# EthCtrlMeter.net
KiCad netlist of a schematic drawn in EAGLE
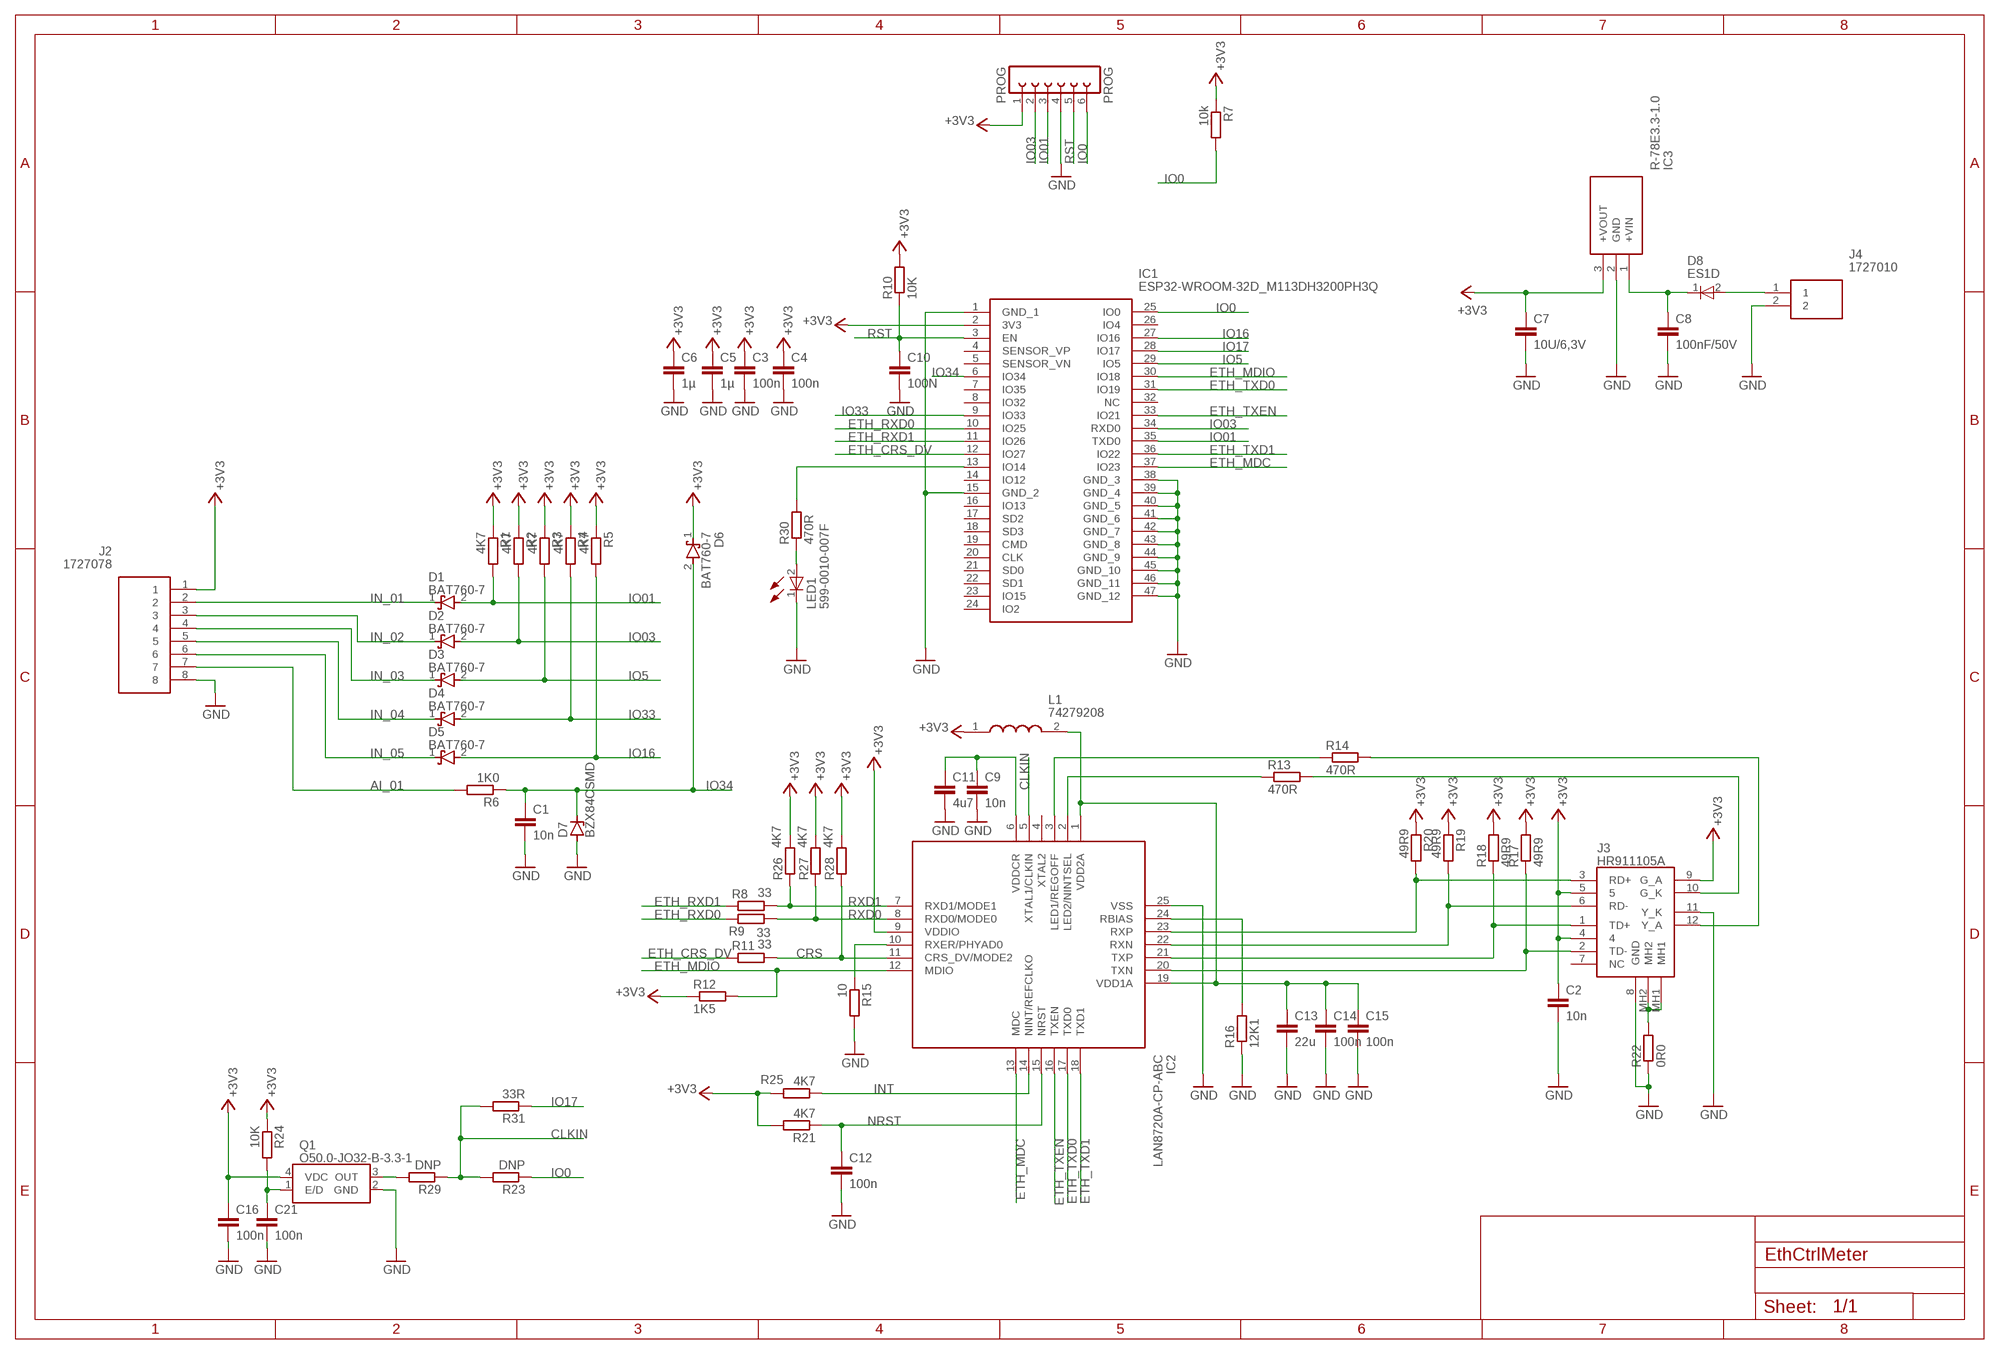
[diagram p0: schematic, sheet 1]

(export (version "E")
  (design (tool "Eeschema 10.0.6"))
  (components
    (comp (ref "C1")
      (value "10n")
      (footprint "eagle-import:C0603")
      (libsource (lib "eagle-import") (part "C-EUC0603"))
    )
    (comp (ref "C2")
      (value "10n")
      (footprint "eagle-import:C0603")
      (libsource (lib "eagle-import") (part "C-EUC0603"))
    )
    (comp (ref "C3")
      (value "100n")
      (footprint "eagle-import:C0603")
      (libsource (lib "eagle-import") (part "C-EUC0603"))
    )
    (comp (ref "C4")
      (value "100n")
      (footprint "eagle-import:C0603")
      (libsource (lib "eagle-import") (part "C-EUC0603"))
    )
    (comp (ref "C5")
      (value "1µ")
      (footprint "eagle-import:C0603")
      (libsource (lib "eagle-import") (part "C-EUC0603"))
    )
    (comp (ref "C6")
      (value "1µ")
      (footprint "eagle-import:C0603")
      (libsource (lib "eagle-import") (part "C-EUC0603"))
    )
    (comp (ref "C7")
      (value "10U/6,3V")
      (footprint "eagle-import:C0603")
      (libsource (lib "eagle-import") (part "C-EUC0603"))
    )
    (comp (ref "C8")
      (value "100nF/50V")
      (footprint "eagle-import:C0603")
      (libsource (lib "eagle-import") (part "C-EUC0603"))
    )
    (comp (ref "C9")
      (value "10n")
      (footprint "eagle-import:C0603")
      (libsource (lib "eagle-import") (part "C-EUC0603"))
    )
    (comp (ref "C10")
      (value "100N")
      (footprint "eagle-import:C0603")
      (libsource (lib "eagle-import") (part "C-EUC0603"))
    )
    (comp (ref "C11")
      (value "4u7")
      (footprint "eagle-import:C0603")
      (libsource (lib "eagle-import") (part "C-EUC0603"))
    )
    (comp (ref "C12")
      (value "100n")
      (footprint "eagle-import:C0603")
      (libsource (lib "eagle-import") (part "C-EUC0603"))
    )
    (comp (ref "C13")
      (value "22u")
      (footprint "eagle-import:C0603")
      (libsource (lib "eagle-import") (part "C-EUC0603"))
    )
    (comp (ref "C14")
      (value "100n")
      (footprint "eagle-import:C0603")
      (libsource (lib "eagle-import") (part "C-EUC0603"))
    )
    (comp (ref "C15")
      (value "100n")
      (footprint "eagle-import:C0603")
      (libsource (lib "eagle-import") (part "C-EUC0603"))
    )
    (comp (ref "C16")
      (value "100n")
      (footprint "eagle-import:C0603")
      (libsource (lib "eagle-import") (part "C-EUC0603"))
    )
    (comp (ref "C21")
      (value "100n")
      (footprint "eagle-import:C0603")
      (libsource (lib "eagle-import") (part "C-EUC0603"))
    )
    (comp (ref "D1")
      (value "BAT760-7")
      (footprint "eagle-import:SOD2513X120N")
      (fields (field (name "MOUSER_PART_NUMBER") "621-BAT760-7"))
      (libsource (lib "eagle-import") (part "BAT760-7"))
    )
    (comp (ref "D2")
      (value "BAT760-7")
      (footprint "eagle-import:SOD2513X120N")
      (fields (field (name "MOUSER_PART_NUMBER") "621-BAT760-7"))
      (libsource (lib "eagle-import") (part "BAT760-7"))
    )
    (comp (ref "D3")
      (value "BAT760-7")
      (footprint "eagle-import:SOD2513X120N")
      (fields (field (name "MOUSER_PART_NUMBER") "621-BAT760-7"))
      (libsource (lib "eagle-import") (part "BAT760-7"))
    )
    (comp (ref "D4")
      (value "BAT760-7")
      (footprint "eagle-import:SOD2513X120N")
      (fields (field (name "MOUSER_PART_NUMBER") "621-BAT760-7"))
      (libsource (lib "eagle-import") (part "BAT760-7"))
    )
    (comp (ref "D5")
      (value "BAT760-7")
      (footprint "eagle-import:SOD2513X120N")
      (fields (field (name "MOUSER_PART_NUMBER") "621-BAT760-7"))
      (libsource (lib "eagle-import") (part "BAT760-7"))
    )
    (comp (ref "D6")
      (value "BAT760-7")
      (footprint "eagle-import:SOD2513X120N")
      (fields (field (name "MOUSER_PART_NUMBER") "621-BAT760-7"))
      (libsource (lib "eagle-import") (part "BAT760-7"))
    )
    (comp (ref "D7")
      (value "BZX84CSMD")
      (footprint "eagle-import:TO236")
      (libsource (lib "eagle-import") (part "BZX84CSMD"))
    )
    (comp (ref "D8")
      (value "ES1D")
      (footprint "eagle-import:SODFL3618X143N")
      (fields
        (field (name "ARROW_PART_NUMBER") "ES1DL R3G")
        (field (name "MOUSER_PART_NUMBER") "821-ES1DLR3G")
      )
      (libsource (lib "eagle-import") (part "ES1DL_R3G"))
    )
    (comp (ref "IC1")
      (value "ESP32-WROOM-32D_M113DH3200PH3Q")
      (footprint "eagle-import:ESP32WROOM32DM113DH3200PH3Q0")
      (fields
        (field (name "MANUFACTURER_PART_NUMBER") "ESP32-WROOM-32D(M113DH3200PH3Q0)")
        (field (name "MOUSER_PART_NUMBER") "356-ESP32WROOM-32D")
      )
      (libsource (lib "eagle-import") (part "ESP32-WROOM-32D_M113DH3200PH3Q"))
    )
    (comp (ref "IC2")
      (value "LAN8720A-CP-ABC")
      (footprint "eagle-import:QFN50P400X400X100-25N")
      (fields (field (name "MOUSER_PART_NUMBER") "579-LAN8720ACPABC"))
      (libsource (lib "eagle-import") (part "LAN8720A-CP-ABC"))
    )
    (comp (ref "IC3")
      (value "R-78E3.3-1.0")
      (footprint "eagle-import:R78E3310")
      (fields (field (name "MOUSER_PART_NUMBER") "919-R-78E3.3-1.0"))
      (libsource (lib "eagle-import") (part "R-78E3.3-1.0"))
    )
    (comp (ref "J2")
      (value "1727078")
      (footprint "eagle-import:1727078")
      (fields (field (name "MOUSER_PART_NUMBER") "651-1727078"))
      (libsource (lib "eagle-import") (part "1727078"))
    )
    (comp (ref "J3")
      (value "HR911105A")
      (footprint "eagle-import:HR911105A")
      (libsource (lib "eagle-import") (part "HR911105A"))
    )
    (comp (ref "J4")
      (value "1727010")
      (footprint "eagle-import:1727010")
      (fields (field (name "MOUSER_PART_NUMBER") "651-1727010"))
      (libsource (lib "eagle-import") (part "1727010"))
    )
    (comp (ref "L1")
      (value "74279208")
      (footprint "eagle-import:CAPC2012X90N")
      (fields (field (name "MOUSER_PART_NUMBER") "710-74279208"))
      (libsource (lib "eagle-import") (part "74279208"))
    )
    (comp (ref "LED1")
      (value "599-0010-007F")
      (footprint "eagle-import:LEDM168X70N")
      (fields (field (name "MOUSER_PART_NUMBER") "645-599-0010-007F"))
      (libsource (lib "eagle-import") (part "599-0010-007F"))
    )
    (comp (ref "PROG")
      (value "PROG")
      (footprint "eagle-import:FE06")
      (libsource (lib "eagle-import") (part "FE06-1"))
    )
    (comp (ref "Q1")
      (value "O50.0-JO32-B-3.3-1")
      (footprint "eagle-import:O200JO32B1V31T1LF")
      (libsource (lib "eagle-import") (part "O50.0-JO32-B-3.3-1"))
    )
    (comp (ref "R1")
      (value "4K7")
      (footprint "eagle-import:R0603")
      (libsource (lib "eagle-import") (part "R-EU_R0603"))
    )
    (comp (ref "R2")
      (value "4K7")
      (footprint "eagle-import:R0603")
      (libsource (lib "eagle-import") (part "R-EU_R0603"))
    )
    (comp (ref "R3")
      (value "4K7")
      (footprint "eagle-import:R0603")
      (libsource (lib "eagle-import") (part "R-EU_R0603"))
    )
    (comp (ref "R4")
      (value "4K7")
      (footprint "eagle-import:R0603")
      (libsource (lib "eagle-import") (part "R-EU_R0603"))
    )
    (comp (ref "R5")
      (value "4K7")
      (footprint "eagle-import:R0603")
      (libsource (lib "eagle-import") (part "R-EU_R0603"))
    )
    (comp (ref "R6")
      (value "1K0")
      (footprint "eagle-import:R0603")
      (libsource (lib "eagle-import") (part "R-EU_R0603"))
    )
    (comp (ref "R7")
      (value "10k")
      (footprint "eagle-import:R0603")
      (libsource (lib "eagle-import") (part "R-EU_R0603"))
    )
    (comp (ref "R8")
      (value "33")
      (footprint "eagle-import:R0603")
      (libsource (lib "eagle-import") (part "R-EU_R0603"))
    )
    (comp (ref "R9")
      (value "33")
      (footprint "eagle-import:R0603")
      (libsource (lib "eagle-import") (part "R-EU_R0603"))
    )
    (comp (ref "R10")
      (value "10K")
      (footprint "eagle-import:R0603")
      (libsource (lib "eagle-import") (part "R-EU_R0603"))
    )
    (comp (ref "R11")
      (value "33")
      (footprint "eagle-import:R0603")
      (libsource (lib "eagle-import") (part "R-EU_R0603"))
    )
    (comp (ref "R12")
      (value "1K5")
      (footprint "eagle-import:R0603")
      (libsource (lib "eagle-import") (part "R-EU_R0603"))
    )
    (comp (ref "R13")
      (value "470R")
      (footprint "eagle-import:R0603")
      (libsource (lib "eagle-import") (part "R-EU_R0603"))
    )
    (comp (ref "R14")
      (value "470R")
      (footprint "eagle-import:R0603")
      (libsource (lib "eagle-import") (part "R-EU_R0603"))
    )
    (comp (ref "R15")
      (value "10")
      (footprint "eagle-import:R0603")
      (libsource (lib "eagle-import") (part "R-EU_R0603"))
    )
    (comp (ref "R16")
      (value "12K1")
      (footprint "eagle-import:R0603")
      (libsource (lib "eagle-import") (part "R-EU_R0603"))
    )
    (comp (ref "R17")
      (value "49R9")
      (footprint "eagle-import:R0603")
      (libsource (lib "eagle-import") (part "R-EU_R0603"))
    )
    (comp (ref "R18")
      (value "49R9")
      (footprint "eagle-import:R0603")
      (libsource (lib "eagle-import") (part "R-EU_R0603"))
    )
    (comp (ref "R19")
      (value "49R9")
      (footprint "eagle-import:R0603")
      (libsource (lib "eagle-import") (part "R-EU_R0603"))
    )
    (comp (ref "R20")
      (value "49R9")
      (footprint "eagle-import:R0603")
      (libsource (lib "eagle-import") (part "R-EU_R0603"))
    )
    (comp (ref "R21")
      (value "4K7")
      (footprint "eagle-import:R0603")
      (libsource (lib "eagle-import") (part "R-EU_R0603"))
    )
    (comp (ref "R22")
      (value "0R0")
      (footprint "eagle-import:R0603")
      (libsource (lib "eagle-import") (part "R-EU_R0603"))
    )
    (comp (ref "R23")
      (value "DNP")
      (footprint "eagle-import:R0603")
      (libsource (lib "eagle-import") (part "R-EU_R0603"))
    )
    (comp (ref "R24")
      (value "10K")
      (footprint "eagle-import:R0603")
      (libsource (lib "eagle-import") (part "R-EU_R0603"))
    )
    (comp (ref "R25")
      (value "4K7")
      (footprint "eagle-import:R0603")
      (libsource (lib "eagle-import") (part "R-EU_R0603"))
    )
    (comp (ref "R26")
      (value "4K7")
      (footprint "eagle-import:R0603")
      (libsource (lib "eagle-import") (part "R-EU_R0603"))
    )
    (comp (ref "R27")
      (value "4K7")
      (footprint "eagle-import:R0603")
      (libsource (lib "eagle-import") (part "R-EU_R0603"))
    )
    (comp (ref "R28")
      (value "4K7")
      (footprint "eagle-import:R0603")
      (libsource (lib "eagle-import") (part "R-EU_R0603"))
    )
    (comp (ref "R29")
      (value "DNP")
      (footprint "eagle-import:R0603")
      (libsource (lib "eagle-import") (part "R-EU_R0603"))
    )
    (comp (ref "R30")
      (value "470R")
      (footprint "eagle-import:R0603")
      (libsource (lib "eagle-import") (part "R-EU_R0603"))
    )
    (comp (ref "R31")
      (value "33R")
      (footprint "eagle-import:R0603")
      (libsource (lib "eagle-import") (part "R-EU_R0603"))
    )
  )
  (nets
    (net (code "1") (name "+3V3") (class "Default")
      (node (ref "C16") (pin "1") (pinfunction "1_1") (pintype "passive"))
      (node (ref "C2") (pin "1") (pinfunction "1_1") (pintype "passive"))
      (node (ref "C3") (pin "1") (pinfunction "1_1") (pintype "passive"))
      (node (ref "C4") (pin "1") (pinfunction "1_1") (pintype "passive"))
      (node (ref "C5") (pin "1") (pinfunction "1_1") (pintype "passive"))
      (node (ref "C6") (pin "1") (pinfunction "1_1") (pintype "passive"))
      (node (ref "C7") (pin "1") (pinfunction "1_1") (pintype "passive"))
      (node (ref "D6") (pin "1") (pinfunction "K_1") (pintype "passive"))
      (node (ref "IC1") (pin "2") (pinfunction "3V3_2") (pintype "bidirectional"))
      (node (ref "IC2") (pin "9") (pinfunction "VDDIO_9") (pintype "bidirectional"))
      (node (ref "IC3") (pin "3") (pinfunction "+VOUT_3") (pintype "bidirectional"))
      (node (ref "J2") (pin "1") (pinfunction "1_1") (pintype "bidirectional"))
      (node (ref "J3") (pin "4") (pinfunction "4_4") (pintype "bidirectional"))
      (node (ref "J3") (pin "5") (pinfunction "5_5") (pintype "bidirectional"))
      (node (ref "J3") (pin "9") (pinfunction "G_A_9") (pintype "bidirectional"))
      (node (ref "L1") (pin "1") (pinfunction "1_1") (pintype "bidirectional"))
      (node (ref "PROG") (pin "1") (pinfunction "1_1") (pintype "passive"))
      (node (ref "Q1") (pin "4") (pinfunction "VDC_4") (pintype "bidirectional"))
      (node (ref "R1") (pin "1") (pinfunction "1_1") (pintype "passive"))
      (node (ref "R10") (pin "2") (pinfunction "2_2") (pintype "passive"))
      (node (ref "R12") (pin "1") (pinfunction "1_1") (pintype "passive"))
      (node (ref "R17") (pin "2") (pinfunction "2_2") (pintype "passive"))
      (node (ref "R18") (pin "2") (pinfunction "2_2") (pintype "passive"))
      (node (ref "R19") (pin "1") (pinfunction "1_1") (pintype "passive"))
      (node (ref "R2") (pin "1") (pinfunction "1_1") (pintype "passive"))
      (node (ref "R20") (pin "1") (pinfunction "1_1") (pintype "passive"))
      (node (ref "R21") (pin "2") (pinfunction "2_2") (pintype "passive"))
      (node (ref "R24") (pin "1") (pinfunction "1_1") (pintype "passive"))
      (node (ref "R25") (pin "2") (pinfunction "2_2") (pintype "passive"))
      (node (ref "R26") (pin "2") (pinfunction "2_2") (pintype "passive"))
      (node (ref "R27") (pin "2") (pinfunction "2_2") (pintype "passive"))
      (node (ref "R28") (pin "2") (pinfunction "2_2") (pintype "passive"))
      (node (ref "R3") (pin "1") (pinfunction "1_1") (pintype "passive"))
      (node (ref "R4") (pin "1") (pinfunction "1_1") (pintype "passive"))
      (node (ref "R5") (pin "1") (pinfunction "1_1") (pintype "passive"))
      (node (ref "R7") (pin "1") (pinfunction "1_1") (pintype "passive"))
    )
    (net (code "2") (name "/AI_01") (class "Default")
      (node (ref "J2") (pin "7") (pinfunction "7_7") (pintype "bidirectional"))
      (node (ref "R6") (pin "2") (pinfunction "2_2") (pintype "passive"))
    )
    (net (code "3") (name "/CLKIN") (class "Default")
      (node (ref "IC2") (pin "5") (pinfunction "XTAL1/CLKIN_5") (pintype "bidirectional"))
      (node (ref "R23") (pin "2") (pinfunction "2_2") (pintype "passive"))
      (node (ref "R29") (pin "1") (pinfunction "1_1") (pintype "passive"))
      (node (ref "R31") (pin "2") (pinfunction "2_2") (pintype "passive"))
    )
    (net (code "4") (name "/CRS") (class "Default")
      (node (ref "IC2") (pin "11") (pinfunction "CRS_DV/MODE2_11") (pintype "bidirectional"))
      (node (ref "R11") (pin "2") (pinfunction "2_2") (pintype "passive"))
      (node (ref "R28") (pin "1") (pinfunction "1_1") (pintype "passive"))
    )
    (net (code "5") (name "/ETH_CRS_DV") (class "Default")
      (node (ref "IC1") (pin "12") (pinfunction "IO27_12") (pintype "bidirectional"))
      (node (ref "R11") (pin "1") (pinfunction "1_1") (pintype "passive"))
    )
    (net (code "6") (name "/ETH_MDC") (class "Default")
      (node (ref "IC1") (pin "37") (pinfunction "IO23_37") (pintype "bidirectional"))
      (node (ref "IC2") (pin "13") (pinfunction "MDC_13") (pintype "bidirectional"))
    )
    (net (code "7") (name "/ETH_MDIO") (class "Default")
      (node (ref "IC1") (pin "30") (pinfunction "IO18_30") (pintype "bidirectional"))
      (node (ref "IC2") (pin "12") (pinfunction "MDIO_12") (pintype "bidirectional"))
      (node (ref "R12") (pin "2") (pinfunction "2_2") (pintype "passive"))
    )
    (net (code "8") (name "/ETH_RXD0") (class "Default")
      (node (ref "IC1") (pin "10") (pinfunction "IO25_10") (pintype "bidirectional"))
      (node (ref "R9") (pin "1") (pinfunction "1_1") (pintype "passive"))
    )
    (net (code "9") (name "/ETH_RXD1") (class "Default")
      (node (ref "IC1") (pin "11") (pinfunction "IO26_11") (pintype "bidirectional"))
      (node (ref "R8") (pin "1") (pinfunction "1_1") (pintype "passive"))
    )
    (net (code "10") (name "/ETH_TXD0") (class "Default")
      (node (ref "IC1") (pin "31") (pinfunction "IO19_31") (pintype "bidirectional"))
      (node (ref "IC2") (pin "17") (pinfunction "TXD0_17") (pintype "bidirectional"))
    )
    (net (code "11") (name "/ETH_TXD1") (class "Default")
      (node (ref "IC1") (pin "36") (pinfunction "IO22_36") (pintype "bidirectional"))
      (node (ref "IC2") (pin "18") (pinfunction "TXD1_18") (pintype "bidirectional"))
    )
    (net (code "12") (name "/ETH_TXEN") (class "Default")
      (node (ref "IC1") (pin "33") (pinfunction "IO21_33") (pintype "bidirectional"))
      (node (ref "IC2") (pin "16") (pinfunction "TXEN_16") (pintype "bidirectional"))
    )
    (net (code "13") (name "/INT") (class "Default")
      (node (ref "IC2") (pin "14") (pinfunction "NINT/REFCLKO_14") (pintype "bidirectional"))
      (node (ref "R25") (pin "1") (pinfunction "1_1") (pintype "passive"))
    )
    (net (code "14") (name "/IN_01") (class "Default")
      (node (ref "D1") (pin "1") (pinfunction "K_1") (pintype "passive"))
      (node (ref "J2") (pin "2") (pinfunction "2_2") (pintype "bidirectional"))
    )
    (net (code "15") (name "/IN_02") (class "Default")
      (node (ref "D2") (pin "1") (pinfunction "K_1") (pintype "passive"))
      (node (ref "J2") (pin "3") (pinfunction "3_3") (pintype "bidirectional"))
    )
    (net (code "16") (name "/IN_03") (class "Default")
      (node (ref "D3") (pin "1") (pinfunction "K_1") (pintype "passive"))
      (node (ref "J2") (pin "4") (pinfunction "4_4") (pintype "bidirectional"))
    )
    (net (code "17") (name "/IN_04") (class "Default")
      (node (ref "D4") (pin "1") (pinfunction "K_1") (pintype "passive"))
      (node (ref "J2") (pin "5") (pinfunction "5_5") (pintype "bidirectional"))
    )
    (net (code "18") (name "/IN_05") (class "Default")
      (node (ref "D5") (pin "1") (pinfunction "K_1") (pintype "passive"))
      (node (ref "J2") (pin "6") (pinfunction "6_6") (pintype "bidirectional"))
    )
    (net (code "19") (name "/IO0") (class "Default")
      (node (ref "IC1") (pin "25") (pinfunction "IO0_25") (pintype "bidirectional"))
      (node (ref "PROG") (pin "6") (pinfunction "6_6") (pintype "passive"))
      (node (ref "R23") (pin "1") (pinfunction "1_1") (pintype "passive"))
      (node (ref "R7") (pin "2") (pinfunction "2_2") (pintype "passive"))
    )
    (net (code "20") (name "/IO01") (class "Default")
      (node (ref "D1") (pin "2") (pinfunction "A_2") (pintype "passive"))
      (node (ref "IC1") (pin "35") (pinfunction "TXD0_35") (pintype "bidirectional"))
      (node (ref "PROG") (pin "3") (pinfunction "3_3") (pintype "passive"))
      (node (ref "R1") (pin "2") (pinfunction "2_2") (pintype "passive"))
    )
    (net (code "21") (name "/IO03") (class "Default")
      (node (ref "D2") (pin "2") (pinfunction "A_2") (pintype "passive"))
      (node (ref "IC1") (pin "34") (pinfunction "RXD0_34") (pintype "bidirectional"))
      (node (ref "PROG") (pin "2") (pinfunction "2_2") (pintype "passive"))
      (node (ref "R2") (pin "2") (pinfunction "2_2") (pintype "passive"))
    )
    (net (code "22") (name "/IO5") (class "Default")
      (node (ref "D3") (pin "2") (pinfunction "A_2") (pintype "passive"))
      (node (ref "IC1") (pin "29") (pinfunction "IO5_29") (pintype "bidirectional"))
      (node (ref "R3") (pin "2") (pinfunction "2_2") (pintype "passive"))
    )
    (net (code "23") (name "/IO16") (class "Default")
      (node (ref "D5") (pin "2") (pinfunction "A_2") (pintype "passive"))
      (node (ref "IC1") (pin "27") (pinfunction "IO16_27") (pintype "bidirectional"))
      (node (ref "R5") (pin "2") (pinfunction "2_2") (pintype "passive"))
    )
    (net (code "24") (name "/IO17") (class "Default")
      (node (ref "IC1") (pin "28") (pinfunction "IO17_28") (pintype "bidirectional"))
      (node (ref "R31") (pin "1") (pinfunction "1_1") (pintype "passive"))
    )
    (net (code "25") (name "/IO33") (class "Default")
      (node (ref "D4") (pin "2") (pinfunction "A_2") (pintype "passive"))
      (node (ref "IC1") (pin "9") (pinfunction "IO33_9") (pintype "bidirectional"))
      (node (ref "R4") (pin "2") (pinfunction "2_2") (pintype "passive"))
    )
    (net (code "26") (name "/IO34") (class "Default")
      (node (ref "C1") (pin "1") (pinfunction "1_1") (pintype "passive"))
      (node (ref "D6") (pin "2") (pinfunction "A_2") (pintype "passive"))
      (node (ref "D7") (pin "C") (pinfunction "C_C") (pintype "passive"))
      (node (ref "IC1") (pin "6") (pinfunction "IO34_6") (pintype "bidirectional"))
      (node (ref "R6") (pin "1") (pinfunction "1_1") (pintype "passive"))
    )
    (net (code "27") (name "/NRST") (class "Default")
      (node (ref "C12") (pin "1") (pinfunction "1_1") (pintype "passive"))
      (node (ref "IC2") (pin "15") (pinfunction "NRST_15") (pintype "bidirectional"))
      (node (ref "R21") (pin "1") (pinfunction "1_1") (pintype "passive"))
    )
    (net (code "28") (name "/RST") (class "Default")
      (node (ref "C10") (pin "1") (pinfunction "1_1") (pintype "passive"))
      (node (ref "IC1") (pin "3") (pinfunction "EN_3") (pintype "bidirectional"))
      (node (ref "PROG") (pin "5") (pinfunction "5_5") (pintype "passive"))
      (node (ref "R10") (pin "1") (pinfunction "1_1") (pintype "passive"))
    )
    (net (code "29") (name "/RXD0") (class "Default")
      (node (ref "IC2") (pin "8") (pinfunction "RXD0/MODE0_8") (pintype "bidirectional"))
      (node (ref "R27") (pin "1") (pinfunction "1_1") (pintype "passive"))
      (node (ref "R9") (pin "2") (pinfunction "2_2") (pintype "passive"))
    )
    (net (code "30") (name "/RXD1") (class "Default")
      (node (ref "IC2") (pin "7") (pinfunction "RXD1/MODE1_7") (pintype "bidirectional"))
      (node (ref "R26") (pin "1") (pinfunction "1_1") (pintype "passive"))
      (node (ref "R8") (pin "2") (pinfunction "2_2") (pintype "passive"))
    )
    (net (code "31") (name "GND") (class "Default")
      (node (ref "C1") (pin "2") (pinfunction "2_2") (pintype "passive"))
      (node (ref "C10") (pin "2") (pinfunction "2_2") (pintype "passive"))
      (node (ref "C11") (pin "2") (pinfunction "2_2") (pintype "passive"))
      (node (ref "C12") (pin "2") (pinfunction "2_2") (pintype "passive"))
      (node (ref "C13") (pin "2") (pinfunction "2_2") (pintype "passive"))
      (node (ref "C14") (pin "2") (pinfunction "2_2") (pintype "passive"))
      (node (ref "C15") (pin "2") (pinfunction "2_2") (pintype "passive"))
      (node (ref "C16") (pin "2") (pinfunction "2_2") (pintype "passive"))
      (node (ref "C2") (pin "2") (pinfunction "2_2") (pintype "passive"))
      (node (ref "C21") (pin "2") (pinfunction "2_2") (pintype "passive"))
      (node (ref "C3") (pin "2") (pinfunction "2_2") (pintype "passive"))
      (node (ref "C4") (pin "2") (pinfunction "2_2") (pintype "passive"))
      (node (ref "C5") (pin "2") (pinfunction "2_2") (pintype "passive"))
      (node (ref "C6") (pin "2") (pinfunction "2_2") (pintype "passive"))
      (node (ref "C7") (pin "2") (pinfunction "2_2") (pintype "passive"))
      (node (ref "C8") (pin "2") (pinfunction "2_2") (pintype "passive"))
      (node (ref "C9") (pin "2") (pinfunction "2_2") (pintype "passive"))
      (node (ref "D7") (pin "A") (pinfunction "A_A") (pintype "passive"))
      (node (ref "IC1") (pin "1") (pinfunction "GND_1_1") (pintype "bidirectional"))
      (node (ref "IC1") (pin "15") (pinfunction "GND_2_15") (pintype "bidirectional"))
      (node (ref "IC1") (pin "38") (pinfunction "GND_3_38") (pintype "bidirectional"))
      (node (ref "IC1") (pin "39") (pinfunction "GND_4_39") (pintype "bidirectional"))
      (node (ref "IC1") (pin "40") (pinfunction "GND_5_40") (pintype "bidirectional"))
      (node (ref "IC1") (pin "41") (pinfunction "GND_6_41") (pintype "bidirectional"))
      (node (ref "IC1") (pin "42") (pinfunction "GND_7_42") (pintype "bidirectional"))
      (node (ref "IC1") (pin "43") (pinfunction "GND_8_43") (pintype "bidirectional"))
      (node (ref "IC1") (pin "44") (pinfunction "GND_9_44") (pintype "bidirectional"))
      (node (ref "IC1") (pin "45") (pinfunction "GND_10_45") (pintype "bidirectional"))
      (node (ref "IC1") (pin "46") (pinfunction "GND_11_46") (pintype "bidirectional"))
      (node (ref "IC1") (pin "47") (pinfunction "GND_12_47") (pintype "bidirectional"))
      (node (ref "IC2") (pin "25") (pinfunction "VSS_25") (pintype "bidirectional"))
      (node (ref "IC3") (pin "2") (pinfunction "GND_2") (pintype "bidirectional"))
      (node (ref "J2") (pin "8") (pinfunction "8_8") (pintype "bidirectional"))
      (node (ref "J3") (pin "11") (pinfunction "Y_K_11") (pintype "bidirectional"))
      (node (ref "J3") (pin "8") (pinfunction "GND_8") (pintype "bidirectional"))
      (node (ref "J4") (pin "2") (pinfunction "2_2") (pintype "bidirectional"))
      (node (ref "LED1") (pin "1") (pinfunction "K_1") (pintype "bidirectional"))
      (node (ref "PROG") (pin "4") (pinfunction "4_4") (pintype "passive"))
      (node (ref "Q1") (pin "2") (pinfunction "GND_2") (pintype "bidirectional"))
      (node (ref "R15") (pin "2") (pinfunction "2_2") (pintype "passive"))
      (node (ref "R16") (pin "1") (pinfunction "1_1") (pintype "passive"))
      (node (ref "R22") (pin "1") (pinfunction "1_1") (pintype "passive"))
    )
    (net (code "32") (name "Net-(D8-A)") (class "Default")
      (node (ref "D8") (pin "2") (pinfunction "A_2") (pintype "bidirectional"))
      (node (ref "J4") (pin "1") (pinfunction "1_1") (pintype "bidirectional"))
    )
    (net (code "33") (name "Net-(D8-K)") (class "Default")
      (node (ref "C8") (pin "1") (pinfunction "1_1") (pintype "passive"))
      (node (ref "D8") (pin "1") (pinfunction "K_1") (pintype "bidirectional"))
      (node (ref "IC3") (pin "1") (pinfunction "+VIN_1") (pintype "bidirectional"))
    )
    (net (code "34") (name "Net-(IC1-IO14)") (class "Default")
      (node (ref "IC1") (pin "13") (pinfunction "IO14_13") (pintype "bidirectional"))
      (node (ref "R30") (pin "2") (pinfunction "2_2") (pintype "passive"))
    )
    (net (code "35") (name "Net-(IC2-LED1{slash}REGOFF)") (class "Default")
      (node (ref "IC2") (pin "3") (pinfunction "LED1/REGOFF_3") (pintype "bidirectional"))
      (node (ref "R14") (pin "1") (pinfunction "1_1") (pintype "passive"))
    )
    (net (code "36") (name "Net-(IC2-LED2{slash}NINTSEL)") (class "Default")
      (node (ref "IC2") (pin "2") (pinfunction "LED2/NINTSEL_2") (pintype "bidirectional"))
      (node (ref "R13") (pin "1") (pinfunction "1_1") (pintype "passive"))
    )
    (net (code "37") (name "Net-(IC2-RBIAS)") (class "Default")
      (node (ref "IC2") (pin "24") (pinfunction "RBIAS_24") (pintype "bidirectional"))
      (node (ref "R16") (pin "2") (pinfunction "2_2") (pintype "passive"))
    )
    (net (code "38") (name "Net-(IC2-RXER{slash}PHYAD0)") (class "Default")
      (node (ref "IC2") (pin "10") (pinfunction "RXER/PHYAD0_10") (pintype "bidirectional"))
      (node (ref "R15") (pin "1") (pinfunction "1_1") (pintype "passive"))
    )
    (net (code "39") (name "Net-(IC2-RXN)") (class "Default")
      (node (ref "IC2") (pin "22") (pinfunction "RXN_22") (pintype "bidirectional"))
      (node (ref "J3") (pin "6") (pinfunction "RD-_6") (pintype "bidirectional"))
      (node (ref "R19") (pin "2") (pinfunction "2_2") (pintype "passive"))
    )
    (net (code "40") (name "Net-(IC2-RXP)") (class "Default")
      (node (ref "IC2") (pin "23") (pinfunction "RXP_23") (pintype "bidirectional"))
      (node (ref "J3") (pin "3") (pinfunction "RD+_3") (pintype "bidirectional"))
      (node (ref "R20") (pin "2") (pinfunction "2_2") (pintype "passive"))
    )
    (net (code "41") (name "Net-(IC2-TXN)") (class "Default")
      (node (ref "IC2") (pin "20") (pinfunction "TXN_20") (pintype "bidirectional"))
      (node (ref "J3") (pin "2") (pinfunction "TD-_2") (pintype "bidirectional"))
      (node (ref "R17") (pin "1") (pinfunction "1_1") (pintype "passive"))
    )
    (net (code "42") (name "Net-(IC2-TXP)") (class "Default")
      (node (ref "IC2") (pin "21") (pinfunction "TXP_21") (pintype "bidirectional"))
      (node (ref "J3") (pin "1") (pinfunction "TD+_1") (pintype "bidirectional"))
      (node (ref "R18") (pin "1") (pinfunction "1_1") (pintype "passive"))
    )
    (net (code "43") (name "Net-(IC2-VDD1A)") (class "Default")
      (node (ref "C13") (pin "1") (pinfunction "1_1") (pintype "passive"))
      (node (ref "C14") (pin "1") (pinfunction "1_1") (pintype "passive"))
      (node (ref "C15") (pin "1") (pinfunction "1_1") (pintype "passive"))
      (node (ref "IC2") (pin "1") (pinfunction "VDD2A_1") (pintype "bidirectional"))
      (node (ref "IC2") (pin "19") (pinfunction "VDD1A_19") (pintype "bidirectional"))
      (node (ref "L1") (pin "2") (pinfunction "2_2") (pintype "bidirectional"))
    )
    (net (code "44") (name "Net-(IC2-VDDCR)") (class "Default")
      (node (ref "C11") (pin "1") (pinfunction "1_1") (pintype "passive"))
      (node (ref "C9") (pin "1") (pinfunction "1_1") (pintype "passive"))
      (node (ref "IC2") (pin "6") (pinfunction "VDDCR_6") (pintype "bidirectional"))
    )
    (net (code "45") (name "Net-(J3-G_K)") (class "Default")
      (node (ref "J3") (pin "10") (pinfunction "G_K_10") (pintype "bidirectional"))
      (node (ref "R13") (pin "2") (pinfunction "2_2") (pintype "passive"))
    )
    (net (code "46") (name "Net-(J3-PadMH1)") (class "Default")
      (node (ref "J3") (pin "MH1") (pinfunction "MH1_MH1") (pintype "bidirectional"))
      (node (ref "J3") (pin "MH2") (pinfunction "MH2_MH2") (pintype "bidirectional"))
      (node (ref "R22") (pin "2") (pinfunction "2_2") (pintype "passive"))
    )
    (net (code "47") (name "Net-(J3-Y_A)") (class "Default")
      (node (ref "J3") (pin "12") (pinfunction "Y_A_12") (pintype "bidirectional"))
      (node (ref "R14") (pin "2") (pinfunction "2_2") (pintype "passive"))
    )
    (net (code "48") (name "Net-(LED1-A)") (class "Default")
      (node (ref "LED1") (pin "2") (pinfunction "A_2") (pintype "bidirectional"))
      (node (ref "R30") (pin "1") (pinfunction "1_1") (pintype "passive"))
    )
    (net (code "49") (name "Net-(Q1-E{slash}D)") (class "Default")
      (node (ref "C21") (pin "1") (pinfunction "1_1") (pintype "passive"))
      (node (ref "Q1") (pin "1") (pinfunction "E/D_1") (pintype "bidirectional"))
      (node (ref "R24") (pin "2") (pinfunction "2_2") (pintype "passive"))
    )
    (net (code "50") (name "Net-(Q1-OUT)") (class "Default")
      (node (ref "Q1") (pin "3") (pinfunction "OUT_3") (pintype "bidirectional"))
      (node (ref "R29") (pin "2") (pinfunction "2_2") (pintype "passive"))
    )
    (net (code "51") (name "unconnected-(IC1-CLK-Pad20)") (class "Default")
      (node (ref "IC1") (pin "20") (pinfunction "CLK_20") (pintype "bidirectional"))
    )
    (net (code "52") (name "unconnected-(IC1-CMD-Pad19)") (class "Default")
      (node (ref "IC1") (pin "19") (pinfunction "CMD_19") (pintype "bidirectional"))
    )
    (net (code "53") (name "unconnected-(IC1-IO2-Pad24)") (class "Default")
      (node (ref "IC1") (pin "24") (pinfunction "IO2_24") (pintype "bidirectional"))
    )
    (net (code "54") (name "unconnected-(IC1-IO4-Pad26)") (class "Default")
      (node (ref "IC1") (pin "26") (pinfunction "IO4_26") (pintype "bidirectional"))
    )
    (net (code "55") (name "unconnected-(IC1-IO12-Pad14)") (class "Default")
      (node (ref "IC1") (pin "14") (pinfunction "IO12_14") (pintype "bidirectional"))
    )
    (net (code "56") (name "unconnected-(IC1-IO13-Pad16)") (class "Default")
      (node (ref "IC1") (pin "16") (pinfunction "IO13_16") (pintype "bidirectional"))
    )
    (net (code "57") (name "unconnected-(IC1-IO15-Pad23)") (class "Default")
      (node (ref "IC1") (pin "23") (pinfunction "IO15_23") (pintype "bidirectional"))
    )
    (net (code "58") (name "unconnected-(IC1-IO32-Pad8)") (class "Default")
      (node (ref "IC1") (pin "8") (pinfunction "IO32_8") (pintype "bidirectional"))
    )
    (net (code "59") (name "unconnected-(IC1-IO35-Pad7)") (class "Default")
      (node (ref "IC1") (pin "7") (pinfunction "IO35_7") (pintype "bidirectional"))
    )
    (net (code "60") (name "unconnected-(IC1-NC-Pad32)") (class "Default")
      (node (ref "IC1") (pin "32") (pinfunction "NC_32") (pintype "no_connect"))
    )
    (net (code "61") (name "unconnected-(IC1-SD0-Pad21)") (class "Default")
      (node (ref "IC1") (pin "21") (pinfunction "SD0_21") (pintype "bidirectional"))
    )
    (net (code "62") (name "unconnected-(IC1-SD1-Pad22)") (class "Default")
      (node (ref "IC1") (pin "22") (pinfunction "SD1_22") (pintype "bidirectional"))
    )
    (net (code "63") (name "unconnected-(IC1-SD2-Pad17)") (class "Default")
      (node (ref "IC1") (pin "17") (pinfunction "SD2_17") (pintype "bidirectional"))
    )
    (net (code "64") (name "unconnected-(IC1-SD3-Pad18)") (class "Default")
      (node (ref "IC1") (pin "18") (pinfunction "SD3_18") (pintype "bidirectional"))
    )
    (net (code "65") (name "unconnected-(IC1-SENSOR_VN-Pad5)") (class "Default")
      (node (ref "IC1") (pin "5") (pinfunction "SENSOR_VN_5") (pintype "bidirectional"))
    )
    (net (code "66") (name "unconnected-(IC1-SENSOR_VP-Pad4)") (class "Default")
      (node (ref "IC1") (pin "4") (pinfunction "SENSOR_VP_4") (pintype "bidirectional"))
    )
    (net (code "67") (name "unconnected-(IC2-XTAL2-Pad4)") (class "Default")
      (node (ref "IC2") (pin "4") (pinfunction "XTAL2_4") (pintype "bidirectional"))
    )
    (net (code "68") (name "unconnected-(J3-NC-Pad7)") (class "Default")
      (node (ref "J3") (pin "7") (pinfunction "NC_7") (pintype "bidirectional"))
    )
  )
)
